# HX711.net
KiCad netlist of a schematic drawn in Altium Designer
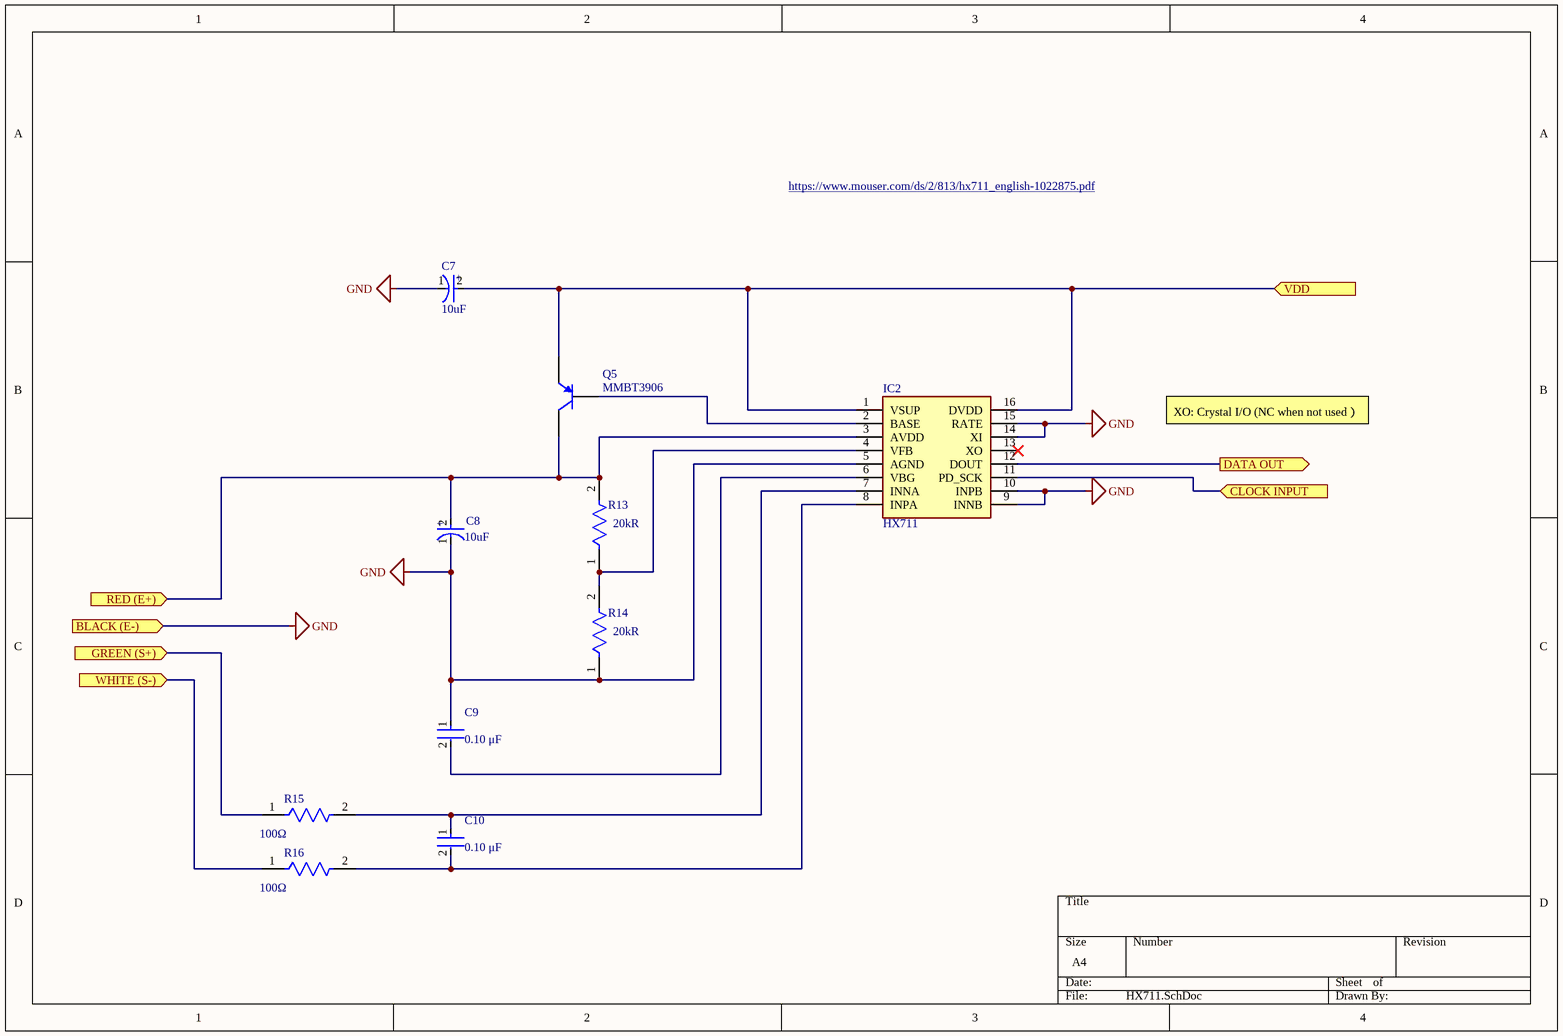
[diagram p0: HX711.SchDoc]

(export (version "E")
  (design (tool "Eeschema 10.0.6"))
  (components
    (comp (ref "C7")
      (value "EDK106M035A9BAA")
      (footprint "FP-EDK9B-MFG")
      (description "CAP ALUM 10UF 20% 35V SMD")
      (fields
        (field (name "CAPACITANCE") "10uF")
        (field (name "MANUFACTURER") "Kemet")
        (field (name "OCTOPART") "https://octopart.com/edk106m035a9baa-kemet-26722193")
      )
      (libsource (lib "Altium Content Vault") (part "cf48714ba7e38822c1575c7ec0b6d1f"))
    )
    (comp (ref "C8")
      (value "EDK106M035A9BAA")
      (footprint "FP-EDK9B-MFG")
      (description "CAP ALUM 10UF 20% 35V SMD")
      (fields
        (field (name "CAPACITANCE") "10uF")
        (field (name "MANUFACTURER") "Kemet")
        (field (name "OCTOPART") "https://octopart.com/edk106m035a9baa-kemet-26722193")
      )
      (libsource (lib "Altium Content Vault") (part "cf48714ba7e38822c1575c7ec0b6d1f"))
    )
    (comp (ref "C9")
      (value "0.10 μF")
      (footprint "FP-C0603C-CF-MFG")
      (description "CAP CER 0.1UF 25V X7R 0603")
      (fields
        (field (name "OCTOPART") "https://octopart.com/c0603c104k3rac7411-kemet-9138804")
        (field (name "MANUFACTURER") "KEMET")
      )
      (libsource (lib "Altium Content Vault") (part "b4654b650e69147ec39a6b967a45e02"))
    )
    (comp (ref "C10")
      (value "0.10 μF")
      (footprint "FP-C0603C-CF-MFG")
      (description "CAP CER 0.1UF 25V X7R 0603")
      (fields
        (field (name "OCTOPART") "https://octopart.com/c0603c104k3rac7411-kemet-9138804")
        (field (name "MANUFACTURER") "KEMET")
      )
      (libsource (lib "Altium Content Vault") (part "b4654b650e69147ec39a6b967a45e02"))
    )
    (comp (ref "IC2")
      (value "HX711")
      (footprint "SamacSys:SOIC127P600X160-16N")
      (description "Integrated Circuit")
      (libsource (lib "*") (part "HX711"))
    )
    (comp (ref "Q5")
      (value "MMBT3906")
      (footprint "FAIR-SOT23-3_V")
      (description "PNP General-Purpose Amplifier, 40 V, 0.2 A, -55 to 150 degC, 3-Pin SOT23, RoHS, Tape and Reel")
      (fields (field (name "TOLERANCE") "20%"))
      (libsource (lib "Altium Content Vault") (part "BJT-PNP-BEC-3"))
    )
    (comp (ref "R13")
      (value "CRCW060320K0FKEAHP")
      (footprint "FP-CRCW0603-HPe3-MFG")
      (description "RES Thick Film, 20kΩ, 1%, 0.33W, 100ppm/°C, 0603")
      (fields (field (name "RESISTANCE") "20kR") (field (name "TOLERANCE") "1%"))
      (libsource (lib "Altium Content Vault") (part "1029c3af85768c4190bb7ad29bc67b5"))
    )
    (comp (ref "R14")
      (value "CRCW060320K0FKEAHP")
      (footprint "FP-CRCW0603-HPe3-MFG")
      (description "RES Thick Film, 20kΩ, 1%, 0.33W, 100ppm/°C, 0603")
      (fields (field (name "RESISTANCE") "20kR") (field (name "TOLERANCE") "1%"))
      (libsource (lib "Altium Content Vault") (part "1029c3af85768c4190bb7ad29bc67b5"))
    )
    (comp (ref "R15")
      (value "100Ω")
      (footprint "FP-RT0603-MFG")
      (description "RES SMD 100 OHM 1% 1/10W 0603")
      (fields
        (field (name "MANUFACTURER PART NUMBER") "RT0603FRE07100RL")
        (field (name "MANUFACTURER") "Yageo")
      )
      (libsource (lib "Altium Content Vault") (part "1029c3af85768c4190bb7ad29bc67b5"))
    )
    (comp (ref "R16")
      (value "100Ω")
      (footprint "FP-RT0603-MFG")
      (description "RES SMD 100 OHM 1% 1/10W 0603")
      (fields
        (field (name "MANUFACTURER PART NUMBER") "RT0603FRE07100RL")
        (field (name "MANUFACTURER") "Yageo")
      )
      (libsource (lib "Altium Content Vault") (part "1029c3af85768c4190bb7ad29bc67b5"))
    )
  )
  (nets
    (net (code "1") (name "/CLOCK INPUT") (class "Default")
      (node (ref "IC2") (pin "11") (pinfunction "PD_SCK_11") (pintype "passive"))
    )
    (net (code "2") (name "/DATA OUT") (class "Default")
      (node (ref "IC2") (pin "12") (pinfunction "DOUT_12") (pintype "passive"))
    )
    (net (code "3") (name "/GREEN (S+)") (class "Default")
      (node (ref "R15") (pin "1") (pinfunction "1_1") (pintype "passive"))
    )
    (net (code "4") (name "/RED (E+)") (class "Default")
      (node (ref "C8") (pin "2") (pinfunction "A_2") (pintype "passive"))
      (node (ref "IC2") (pin "3") (pinfunction "AVDD_3") (pintype "passive"))
      (node (ref "Q5") (pin "3") (pinfunction "C_3") (pintype "passive"))
      (node (ref "R13") (pin "2") (pinfunction "2_2") (pintype "passive"))
    )
    (net (code "5") (name "/VDD") (class "Default")
      (node (ref "C7") (pin "2") (pinfunction "A_2") (pintype "passive"))
      (node (ref "IC2") (pin "1") (pinfunction "VSUP_1") (pintype "passive"))
      (node (ref "IC2") (pin "16") (pinfunction "DVDD_16") (pintype "passive"))
      (node (ref "Q5") (pin "2") (pinfunction "E_2") (pintype "passive"))
    )
    (net (code "6") (name "/WHITE (S-)") (class "Default")
      (node (ref "R16") (pin "1") (pinfunction "1_1") (pintype "passive"))
    )
    (net (code "7") (name "GND") (class "Default")
      (node (ref "C7") (pin "1") (pinfunction "C_1") (pintype "passive"))
      (node (ref "C8") (pin "1") (pinfunction "C_1") (pintype "passive"))
      (node (ref "C9") (pin "1") (pinfunction "1_1") (pintype "passive"))
      (node (ref "IC2") (pin "10") (pinfunction "INPB_10") (pintype "passive"))
      (node (ref "IC2") (pin "14") (pinfunction "XI_14") (pintype "passive"))
      (node (ref "IC2") (pin "15") (pinfunction "RATE_15") (pintype "passive"))
      (node (ref "IC2") (pin "5") (pinfunction "AGND_5") (pintype "passive"))
      (node (ref "IC2") (pin "9") (pinfunction "INNB_9") (pintype "passive"))
      (node (ref "R14") (pin "1") (pinfunction "1_1") (pintype "passive"))
    )
    (net (code "8") (name "Net-(IC2-BASE)") (class "Default")
      (node (ref "IC2") (pin "2") (pinfunction "BASE_2") (pintype "passive"))
      (node (ref "Q5") (pin "1") (pinfunction "B_1") (pintype "passive"))
    )
    (net (code "9") (name "Net-(IC2-INNA)") (class "Default")
      (node (ref "C10") (pin "1") (pinfunction "1_1") (pintype "passive"))
      (node (ref "IC2") (pin "7") (pinfunction "INNA_7") (pintype "passive"))
      (node (ref "R15") (pin "2") (pinfunction "2_2") (pintype "passive"))
    )
    (net (code "10") (name "Net-(IC2-INPA)") (class "Default")
      (node (ref "C10") (pin "2") (pinfunction "2_2") (pintype "passive"))
      (node (ref "IC2") (pin "8") (pinfunction "INPA_8") (pintype "passive"))
      (node (ref "R16") (pin "2") (pinfunction "2_2") (pintype "passive"))
    )
    (net (code "11") (name "Net-(IC2-VBG)") (class "Default")
      (node (ref "C9") (pin "2") (pinfunction "2_2") (pintype "passive"))
      (node (ref "IC2") (pin "6") (pinfunction "VBG_6") (pintype "passive"))
    )
    (net (code "12") (name "Net-(IC2-VFB)") (class "Default")
      (node (ref "IC2") (pin "4") (pinfunction "VFB_4") (pintype "passive"))
      (node (ref "R13") (pin "1") (pinfunction "1_1") (pintype "passive"))
      (node (ref "R14") (pin "2") (pinfunction "2_2") (pintype "passive"))
    )
    (net (code "13") (name "unconnected-(IC2-XO-Pad13)") (class "Default")
      (node (ref "IC2") (pin "13") (pinfunction "XO_13") (pintype "passive+no_connect"))
    )
  )
)
